# Singularitron_Flashlight_Module_v1.net
KiCad netlist of a schematic drawn in EAGLE
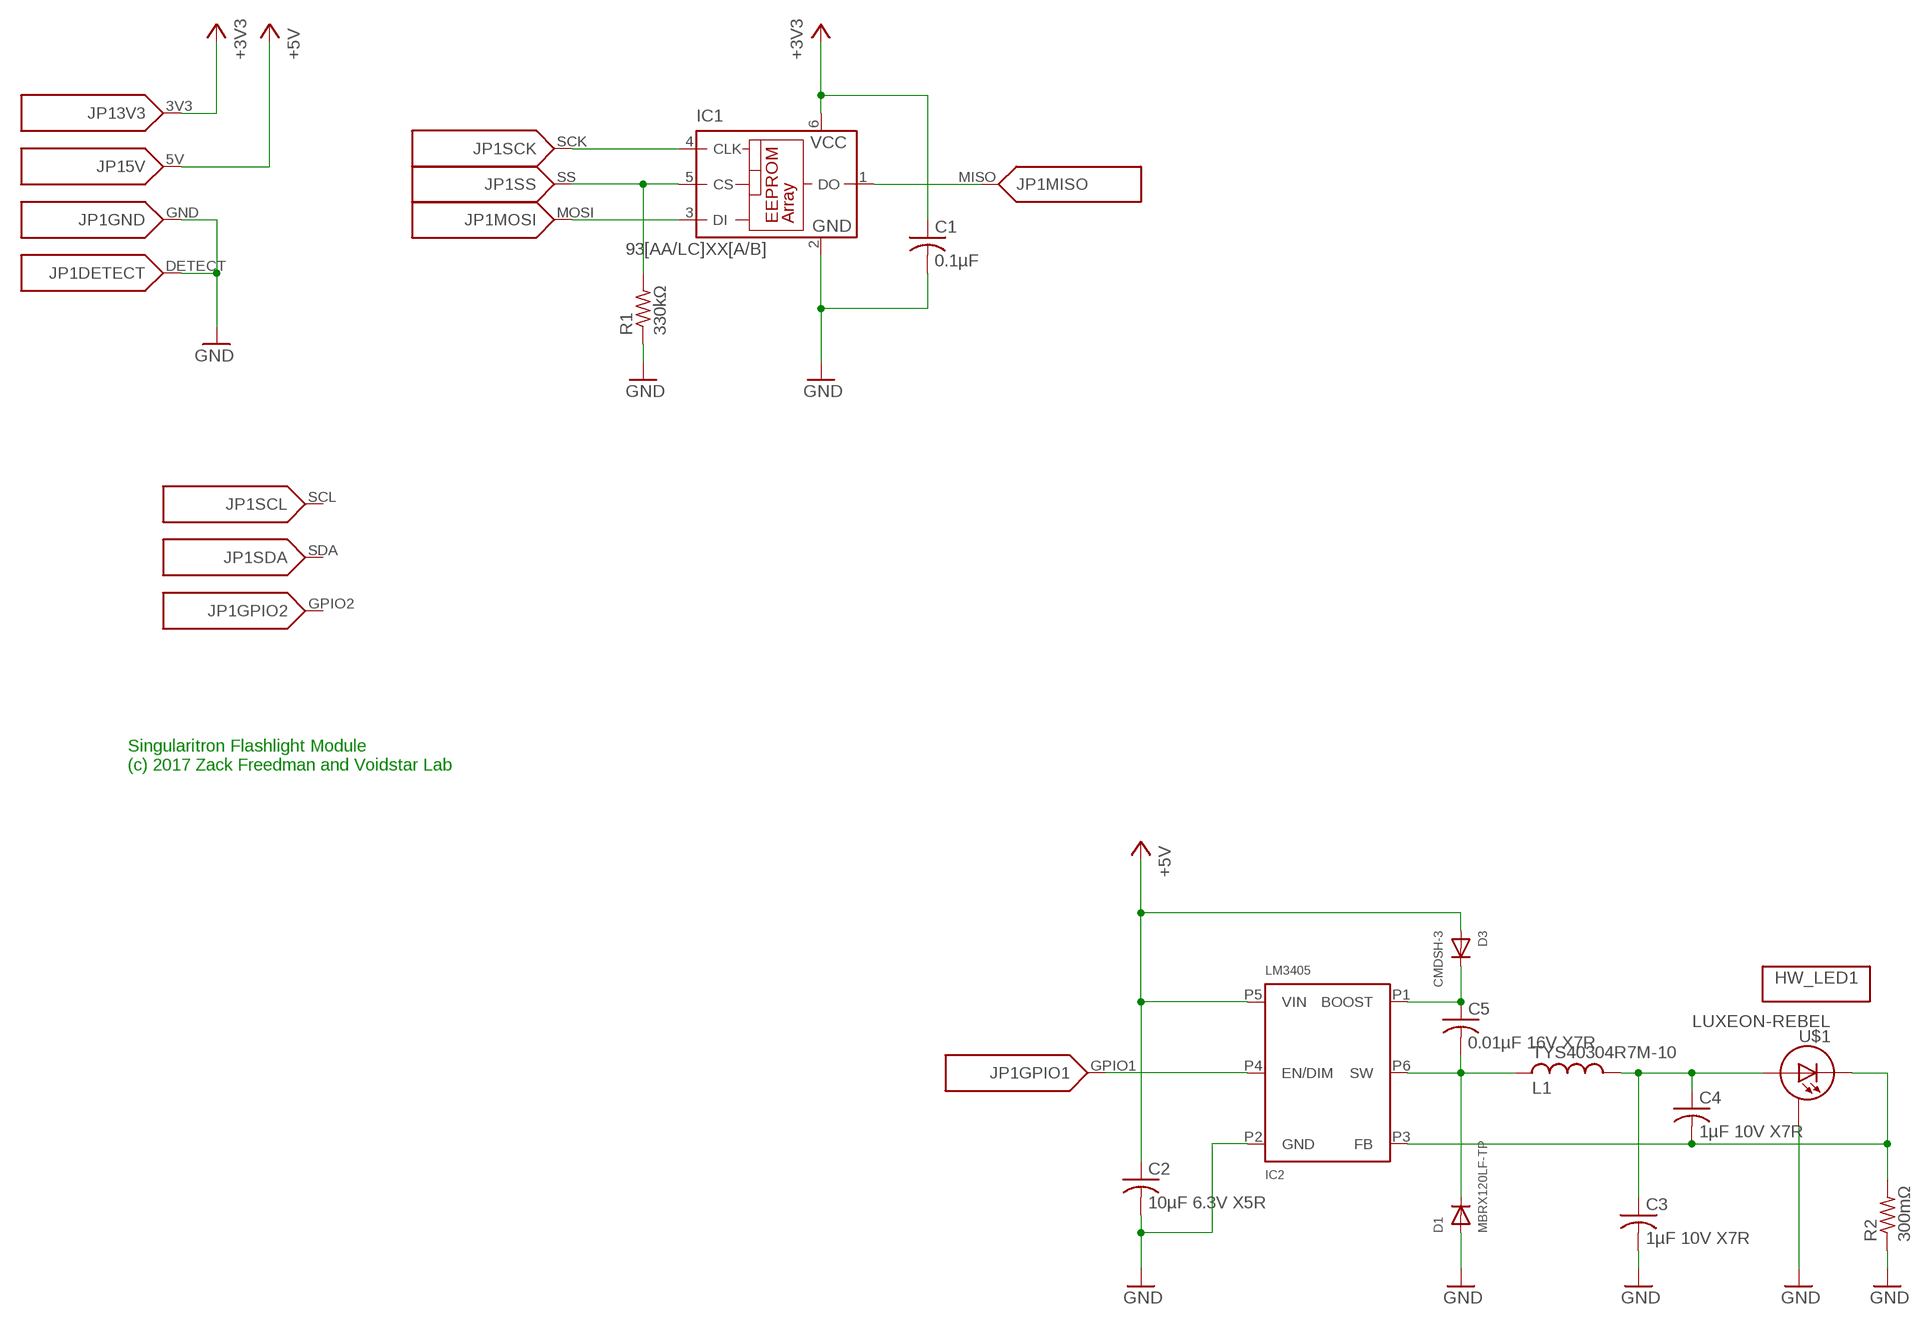
[diagram p0: schematic, sheet 1]

(export (version "E")
  (design (tool "Eeschema 10.0.6"))
  (components
    (comp (ref "C1")
      (value "0.1µF")
      (footprint "eagle-import:C0603")
      (libsource (lib "eagle-import") (part "C-USC0603"))
    )
    (comp (ref "C2")
      (value "10µF 6.3V X5R")
      (footprint "eagle-import:C0805")
      (libsource (lib "eagle-import") (part "C-USC0805"))
    )
    (comp (ref "C3")
      (value "1µF 10V X7R")
      (footprint "eagle-import:C0805")
      (libsource (lib "eagle-import") (part "C-USC0805"))
    )
    (comp (ref "C4")
      (value "1µF 10V X7R")
      (footprint "eagle-import:C0805")
      (libsource (lib "eagle-import") (part "C-USC0805"))
    )
    (comp (ref "C5")
      (value "0.01µF 16V X7R")
      (footprint "eagle-import:C0603")
      (libsource (lib "eagle-import") (part "C-USC0603"))
    )
    (comp (ref "D1")
      (value "MBRX120LF-TP")
      (footprint "eagle-import:SOD-123")
      (libsource (lib "eagle-import") (part "DIODESOD-123"))
    )
    (comp (ref "D3")
      (value "CMDSH-3")
      (footprint "eagle-import:SOD-323F")
      (libsource (lib "eagle-import") (part "DIODESOD-323F"))
    )
    (comp (ref "HW_LED1")
      (value "CARCLO_10771_10772")
      (footprint "eagle-import:CARCLO_10MM_NARROW_MEDIUM")
      (libsource (lib "eagle-import") (part "CARCLO_10771_10772"))
    )
    (comp (ref "IC1")
      (value "93[AA/LC]XX[A/B]")
      (footprint "eagle-import:SOT23-6")
      (fields (field (name "MPN") "93AA76AT-I/OT"))
      (libsource (lib "eagle-import") (part "9376?AAA"))
    )
    (comp (ref "IC2")
      (value "LM3405")
      (footprint "eagle-import:SOT-23")
      (libsource (lib "eagle-import") (part "LM3405"))
    )
    (comp (ref "JP1")
      (value "SINGULARITRON_CART_BASE")
      (footprint "eagle-import:SINGULARITRON_CART_BASE")
      (libsource (lib "eagle-import") (part "SINGULARITRON_CART_BASE"))
    )
    (comp (ref "L1")
      (value "TYS40304R7M-10")
      (footprint "eagle-import:TYS40304R7M-10")
      (libsource (lib "eagle-import") (part "TYS40304R7M-10"))
    )
    (comp (ref "R1")
      (value "330kΩ")
      (footprint "eagle-import:R0603")
      (libsource (lib "eagle-import") (part "R-US_R0603"))
    )
    (comp (ref "R2")
      (value "300mΩ")
      (footprint "eagle-import:R0805")
      (libsource (lib "eagle-import") (part "R-US_R0805"))
    )
    (comp (ref "U$1")
      (value "LUXEON-REBEL")
      (footprint "eagle-import:LUXEON-REBEL")
      (libsource (lib "eagle-import") (part "LUXEON-REBEL"))
    )
  )
  (nets
    (net (code "1") (name "+3V3") (class "Default")
      (node (ref "C1") (pin "1") (pinfunction "1_1") (pintype "passive"))
      (node (ref "IC1") (pin "6") (pinfunction "VCC_6") (pintype "power_in"))
      (node (ref "JP1") (pin "3V3") (pinfunction "P$1_3V3") (pintype "bidirectional"))
    )
    (net (code "2") (name "+5V") (class "Default")
      (node (ref "C2") (pin "1") (pinfunction "1_1") (pintype "passive"))
      (node (ref "D3") (pin "A") (pinfunction "A_A") (pintype "passive"))
      (node (ref "IC2") (pin "P5") (pinfunction "VIN_P5") (pintype "bidirectional"))
      (node (ref "JP1") (pin "5V") (pinfunction "P$1_5V") (pintype "bidirectional"))
    )
    (net (code "3") (name "GND") (class "Default")
      (node (ref "C1") (pin "2") (pinfunction "2_2") (pintype "passive"))
      (node (ref "C2") (pin "2") (pinfunction "2_2") (pintype "passive"))
      (node (ref "C3") (pin "2") (pinfunction "2_2") (pintype "passive"))
      (node (ref "D1") (pin "A") (pinfunction "A_A") (pintype "passive"))
      (node (ref "IC1") (pin "2") (pinfunction "GND_2") (pintype "power_in"))
      (node (ref "IC2") (pin "P2") (pinfunction "GND_P2") (pintype "bidirectional"))
      (node (ref "JP1") (pin "DETECT") (pinfunction "P$1_DETECT") (pintype "bidirectional"))
      (node (ref "JP1") (pin "GND") (pinfunction "P$1_GND") (pintype "bidirectional"))
      (node (ref "R1") (pin "1") (pinfunction "1_1") (pintype "passive"))
      (node (ref "R2") (pin "1") (pinfunction "1_1") (pintype "passive"))
      (node (ref "U$1") (pin "P$3") (pinfunction "S_P$3") (pintype "bidirectional"))
    )
    (net (code "4") (name "Net-(IC1-CLK)") (class "Default")
      (node (ref "IC1") (pin "4") (pinfunction "CLK_4") (pintype "input"))
      (node (ref "JP1") (pin "SCK") (pinfunction "P$1_SCK") (pintype "bidirectional"))
    )
    (net (code "5") (name "Net-(IC1-CS)") (class "Default")
      (node (ref "IC1") (pin "5") (pinfunction "CS_5") (pintype "input"))
      (node (ref "JP1") (pin "SS") (pinfunction "P$1_SS") (pintype "bidirectional"))
      (node (ref "R1") (pin "2") (pinfunction "2_2") (pintype "passive"))
    )
    (net (code "6") (name "Net-(IC1-DI)") (class "Default")
      (node (ref "IC1") (pin "3") (pinfunction "DI_3") (pintype "input"))
      (node (ref "JP1") (pin "MOSI") (pinfunction "P$1_MOSI") (pintype "bidirectional"))
    )
    (net (code "7") (name "Net-(IC1-DO)") (class "Default")
      (node (ref "IC1") (pin "1") (pinfunction "DO_1") (pintype "tri_state"))
      (node (ref "JP1") (pin "MISO") (pinfunction "P$1_MISO") (pintype "bidirectional"))
    )
    (net (code "8") (name "Net-(IC2-BOOST)") (class "Default")
      (node (ref "C5") (pin "1") (pinfunction "1_1") (pintype "passive"))
      (node (ref "D3") (pin "C") (pinfunction "C_C") (pintype "passive"))
      (node (ref "IC2") (pin "P1") (pinfunction "BOOST_P1") (pintype "bidirectional"))
    )
    (net (code "9") (name "Net-(IC2-EN{slash}DIM)") (class "Default")
      (node (ref "IC2") (pin "P4") (pinfunction "EN/DIM_P4") (pintype "bidirectional"))
      (node (ref "JP1") (pin "GPIO1") (pinfunction "P$1_GPIO1") (pintype "bidirectional"))
    )
    (net (code "10") (name "Net-(IC2-FB)") (class "Default")
      (node (ref "C4") (pin "2") (pinfunction "2_2") (pintype "passive"))
      (node (ref "IC2") (pin "P3") (pinfunction "FB_P3") (pintype "bidirectional"))
      (node (ref "R2") (pin "2") (pinfunction "2_2") (pintype "passive"))
      (node (ref "U$1") (pin "CATHODE") (pinfunction "C_CATHODE") (pintype "passive"))
    )
    (net (code "11") (name "Net-(IC2-SW)") (class "Default")
      (node (ref "C5") (pin "2") (pinfunction "2_2") (pintype "passive"))
      (node (ref "D1") (pin "C") (pinfunction "C_C") (pintype "passive"))
      (node (ref "IC2") (pin "P6") (pinfunction "SW_P6") (pintype "bidirectional"))
      (node (ref "L1") (pin "P$2") (pinfunction "2_P$2") (pintype "passive"))
    )
    (net (code "12") (name "Net-(L1-1)") (class "Default")
      (node (ref "C3") (pin "1") (pinfunction "1_1") (pintype "passive"))
      (node (ref "C4") (pin "1") (pinfunction "1_1") (pintype "passive"))
      (node (ref "L1") (pin "P$1") (pinfunction "1_P$1") (pintype "passive"))
      (node (ref "U$1") (pin "ANODE") (pinfunction "A_ANODE") (pintype "passive"))
    )
    (net (code "13") (name "unconnected-(JP1F-P$1-PadGPIO2)") (class "Default")
      (node (ref "JP1") (pin "GPIO2") (pinfunction "P$1_GPIO2") (pintype "bidirectional"))
    )
    (net (code "14") (name "unconnected-(JP1J-P$1-PadSCL)") (class "Default")
      (node (ref "JP1") (pin "SCL") (pinfunction "P$1_SCL") (pintype "bidirectional"))
    )
    (net (code "15") (name "unconnected-(JP1K-P$1-PadSDA)") (class "Default")
      (node (ref "JP1") (pin "SDA") (pinfunction "P$1_SDA") (pintype "bidirectional"))
    )
  )
)
